# Input_interface.net
KiCad netlist of a schematic drawn in EAGLE
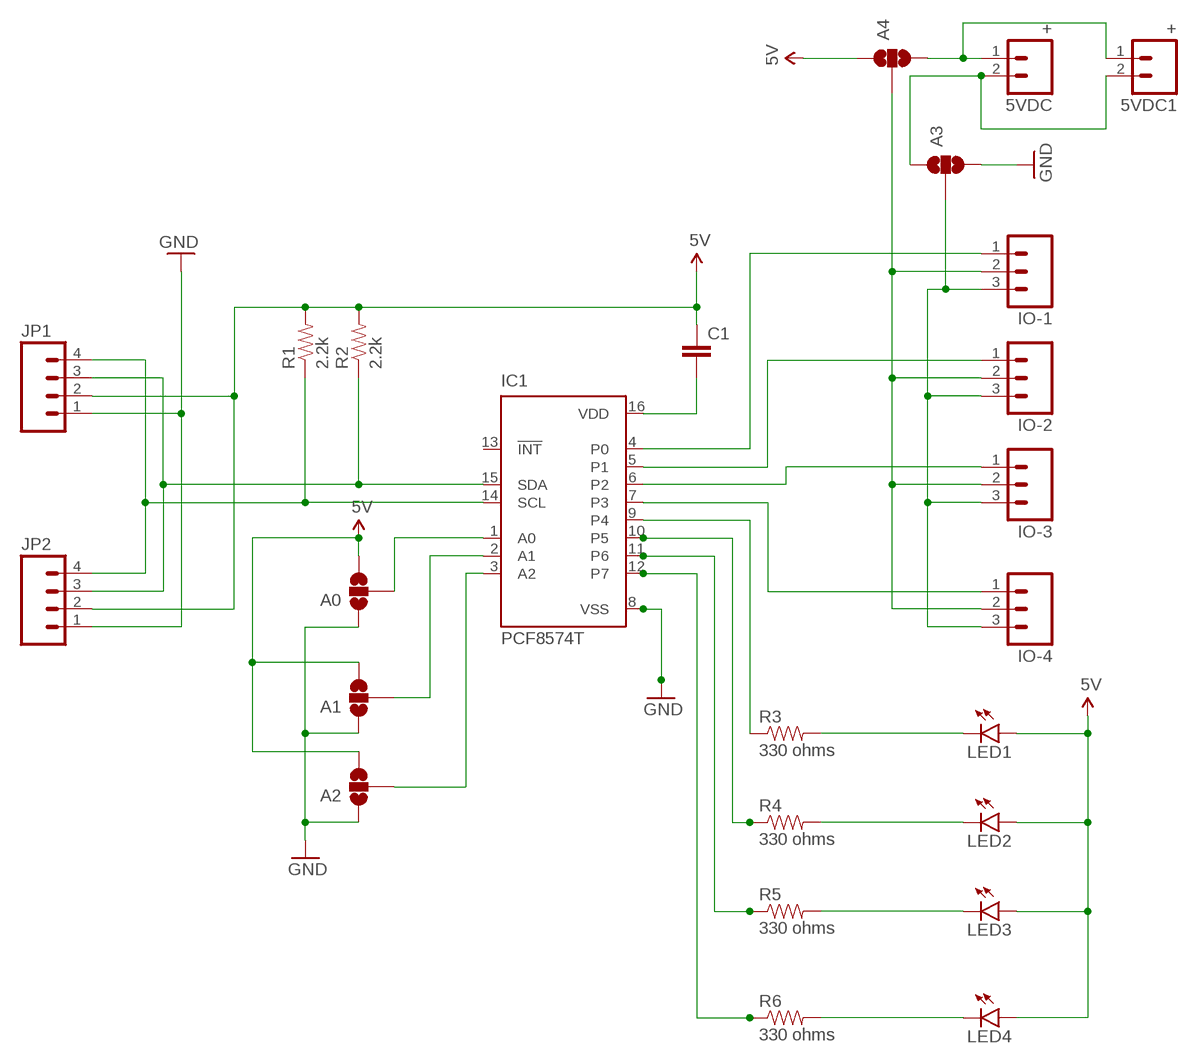
[diagram p0: schematic, sheet 1]

(export (version "E")
  (design (tool "Eeschema 10.0.6"))
  (components
    (comp (ref "5VDC")
      (value "+")
      (footprint "eagle-import:1X02")
      (libsource (lib "eagle-import") (part "M02PTH"))
    )
    (comp (ref "5VDC1")
      (value "+")
      (footprint "eagle-import:1X02")
      (libsource (lib "eagle-import") (part "M02PTH"))
    )
    (comp (ref "A0")
      (value "SOLDERJUMPER_2WAYS")
      (footprint "eagle-import:SJ_3")
      (libsource (lib "eagle-import") (part "SOLDERJUMPER_2WAYS"))
    )
    (comp (ref "A1")
      (value "SOLDERJUMPER_2WAYS")
      (footprint "eagle-import:SJ_3")
      (libsource (lib "eagle-import") (part "SOLDERJUMPER_2WAYS"))
    )
    (comp (ref "A2")
      (value "SOLDERJUMPER_2WAYS")
      (footprint "eagle-import:SJ_3")
      (libsource (lib "eagle-import") (part "SOLDERJUMPER_2WAYS"))
    )
    (comp (ref "A3")
      (value "SOLDERJUMPER_2WAYS")
      (footprint "eagle-import:SJ_3")
      (libsource (lib "eagle-import") (part "SOLDERJUMPER_2WAYS"))
    )
    (comp (ref "A4")
      (value "SOLDERJUMPER_2WAYS")
      (footprint "eagle-import:SJ_3")
      (libsource (lib "eagle-import") (part "SOLDERJUMPER_2WAYS"))
    )
    (comp (ref "C1")
      (value "CAPPTH2")
      (footprint "eagle-import:CAP-PTH-SMALL2")
      (libsource (lib "eagle-import") (part "CAPPTH2"))
    )
    (comp (ref "IC1")
      (value "PCF8574T")
      (footprint "eagle-import:SO16W")
      (libsource (lib "eagle-import") (part "PCF8574T"))
    )
    (comp (ref "IO-1")
      (value "M03PTH")
      (footprint "eagle-import:1X03")
      (libsource (lib "eagle-import") (part "M03PTH"))
    )
    (comp (ref "IO-2")
      (value "M03PTH")
      (footprint "eagle-import:1X03")
      (libsource (lib "eagle-import") (part "M03PTH"))
    )
    (comp (ref "IO-3")
      (value "M03PTH")
      (footprint "eagle-import:1X03")
      (libsource (lib "eagle-import") (part "M03PTH"))
    )
    (comp (ref "IO-4")
      (value "M03PTH")
      (footprint "eagle-import:1X03")
      (libsource (lib "eagle-import") (part "M03PTH"))
    )
    (comp (ref "JP1")
      (value "M04PTH")
      (footprint "eagle-import:1X04")
      (libsource (lib "eagle-import") (part "M04PTH"))
    )
    (comp (ref "JP2")
      (value "M04PTH")
      (footprint "eagle-import:1X04")
      (libsource (lib "eagle-import") (part "M04PTH"))
    )
    (comp (ref "LED1")
      (value "LED3MM")
      (footprint "eagle-import:LED3MM")
      (libsource (lib "eagle-import") (part "LED3MM"))
    )
    (comp (ref "LED2")
      (value "LED3MM")
      (footprint "eagle-import:LED3MM")
      (libsource (lib "eagle-import") (part "LED3MM"))
    )
    (comp (ref "LED3")
      (value "LED3MM")
      (footprint "eagle-import:LED3MM")
      (libsource (lib "eagle-import") (part "LED3MM"))
    )
    (comp (ref "LED4")
      (value "LED3MM")
      (footprint "eagle-import:LED3MM")
      (libsource (lib "eagle-import") (part "LED3MM"))
    )
    (comp (ref "R1")
      (value "2.2k")
      (footprint "eagle-import:AXIAL-0.3")
      (libsource (lib "eagle-import") (part "RESISTORAXIAL-0.3"))
    )
    (comp (ref "R2")
      (value "2.2k")
      (footprint "eagle-import:AXIAL-0.3")
      (libsource (lib "eagle-import") (part "RESISTORAXIAL-0.3"))
    )
    (comp (ref "R3")
      (value "330 ohms")
      (footprint "eagle-import:AXIAL-0.3")
      (libsource (lib "eagle-import") (part "RESISTORAXIAL-0.3"))
    )
    (comp (ref "R4")
      (value "330 ohms")
      (footprint "eagle-import:AXIAL-0.3")
      (libsource (lib "eagle-import") (part "RESISTORAXIAL-0.3"))
    )
    (comp (ref "R5")
      (value "330 ohms")
      (footprint "eagle-import:AXIAL-0.3")
      (libsource (lib "eagle-import") (part "RESISTORAXIAL-0.3"))
    )
    (comp (ref "R6")
      (value "330 ohms")
      (footprint "eagle-import:AXIAL-0.3")
      (libsource (lib "eagle-import") (part "RESISTORAXIAL-0.3"))
    )
  )
  (nets
    (net (code "1") (name "5V") (class "Default")
      (node (ref "A0") (pin "3") (pinfunction "3_3") (pintype "passive"))
      (node (ref "A1") (pin "3") (pinfunction "3_3") (pintype "passive"))
      (node (ref "A2") (pin "3") (pinfunction "3_3") (pintype "passive"))
      (node (ref "A4") (pin "1") (pinfunction "1_1") (pintype "passive"))
      (node (ref "C1") (pin "1") (pinfunction "1_1") (pintype "passive"))
      (node (ref "JP1") (pin "2") (pinfunction "2_2") (pintype "passive"))
      (node (ref "JP2") (pin "2") (pinfunction "2_2") (pintype "passive"))
      (node (ref "LED1") (pin "A") (pinfunction "A_A") (pintype "passive"))
      (node (ref "LED2") (pin "A") (pinfunction "A_A") (pintype "passive"))
      (node (ref "LED3") (pin "A") (pinfunction "A_A") (pintype "passive"))
      (node (ref "LED4") (pin "A") (pinfunction "A_A") (pintype "passive"))
      (node (ref "R1") (pin "P$2") (pinfunction "2_P$2") (pintype "passive"))
      (node (ref "R2") (pin "P$2") (pinfunction "2_P$2") (pintype "passive"))
    )
    (net (code "2") (name "GND") (class "Default")
      (node (ref "A0") (pin "1") (pinfunction "1_1") (pintype "passive"))
      (node (ref "A1") (pin "1") (pinfunction "1_1") (pintype "passive"))
      (node (ref "A2") (pin "1") (pinfunction "1_1") (pintype "passive"))
      (node (ref "A3") (pin "3") (pinfunction "3_3") (pintype "passive"))
      (node (ref "IC1") (pin "8") (pinfunction "VSS_8") (pintype "power_in"))
      (node (ref "JP1") (pin "1") (pinfunction "1_1") (pintype "passive"))
      (node (ref "JP2") (pin "1") (pinfunction "1_1") (pintype "passive"))
    )
    (net (code "3") (name "Net-(5VDC-Pad1)") (class "Default")
      (node (ref "5VDC") (pin "1") (pinfunction "1_1") (pintype "passive"))
      (node (ref "5VDC1") (pin "1") (pinfunction "1_1") (pintype "passive"))
      (node (ref "A4") (pin "3") (pinfunction "3_3") (pintype "passive"))
    )
    (net (code "4") (name "Net-(5VDC-Pad2)") (class "Default")
      (node (ref "5VDC") (pin "2") (pinfunction "2_2") (pintype "passive"))
      (node (ref "5VDC1") (pin "2") (pinfunction "2_2") (pintype "passive"))
      (node (ref "A3") (pin "1") (pinfunction "1_1") (pintype "passive"))
    )
    (net (code "5") (name "Net-(A3-Pad2)") (class "Default")
      (node (ref "A3") (pin "2") (pinfunction "2_2") (pintype "passive"))
      (node (ref "IO-1") (pin "3") (pinfunction "3_3") (pintype "passive"))
      (node (ref "IO-2") (pin "3") (pinfunction "3_3") (pintype "passive"))
      (node (ref "IO-3") (pin "3") (pinfunction "3_3") (pintype "passive"))
      (node (ref "IO-4") (pin "3") (pinfunction "3_3") (pintype "passive"))
    )
    (net (code "6") (name "Net-(A4-Pad2)") (class "Default")
      (node (ref "A4") (pin "2") (pinfunction "2_2") (pintype "passive"))
      (node (ref "IO-1") (pin "2") (pinfunction "2_2") (pintype "passive"))
      (node (ref "IO-2") (pin "2") (pinfunction "2_2") (pintype "passive"))
      (node (ref "IO-3") (pin "2") (pinfunction "2_2") (pintype "passive"))
      (node (ref "IO-4") (pin "2") (pinfunction "2_2") (pintype "passive"))
    )
    (net (code "7") (name "Net-(IC1-A0)") (class "Default")
      (node (ref "A0") (pin "2") (pinfunction "2_2") (pintype "passive"))
      (node (ref "IC1") (pin "1") (pinfunction "A0_1") (pintype "input"))
    )
    (net (code "8") (name "Net-(IC1-A1)") (class "Default")
      (node (ref "A1") (pin "2") (pinfunction "2_2") (pintype "passive"))
      (node (ref "IC1") (pin "2") (pinfunction "A1_2") (pintype "input"))
    )
    (net (code "9") (name "Net-(IC1-A2)") (class "Default")
      (node (ref "A2") (pin "2") (pinfunction "2_2") (pintype "passive"))
      (node (ref "IC1") (pin "3") (pinfunction "A2_3") (pintype "input"))
    )
    (net (code "10") (name "Net-(IC1-P0)") (class "Default")
      (node (ref "IC1") (pin "4") (pinfunction "P0_4") (pintype "bidirectional"))
      (node (ref "IO-1") (pin "1") (pinfunction "1_1") (pintype "passive"))
    )
    (net (code "11") (name "Net-(IC1-P1)") (class "Default")
      (node (ref "IC1") (pin "5") (pinfunction "P1_5") (pintype "bidirectional"))
      (node (ref "IO-2") (pin "1") (pinfunction "1_1") (pintype "passive"))
    )
    (net (code "12") (name "Net-(IC1-P2)") (class "Default")
      (node (ref "IC1") (pin "6") (pinfunction "P2_6") (pintype "bidirectional"))
      (node (ref "IO-3") (pin "1") (pinfunction "1_1") (pintype "passive"))
    )
    (net (code "13") (name "Net-(IC1-P3)") (class "Default")
      (node (ref "IC1") (pin "7") (pinfunction "P3_7") (pintype "bidirectional"))
      (node (ref "IO-4") (pin "1") (pinfunction "1_1") (pintype "passive"))
    )
    (net (code "14") (name "Net-(IC1-P4)") (class "Default")
      (node (ref "IC1") (pin "9") (pinfunction "P4_9") (pintype "bidirectional"))
      (node (ref "R3") (pin "P$1") (pinfunction "1_P$1") (pintype "passive"))
    )
    (net (code "15") (name "Net-(IC1-P5)") (class "Default")
      (node (ref "IC1") (pin "10") (pinfunction "P5_10") (pintype "bidirectional"))
      (node (ref "R4") (pin "P$1") (pinfunction "1_P$1") (pintype "passive"))
    )
    (net (code "16") (name "Net-(IC1-P6)") (class "Default")
      (node (ref "IC1") (pin "11") (pinfunction "P6_11") (pintype "bidirectional"))
      (node (ref "R5") (pin "P$1") (pinfunction "1_P$1") (pintype "passive"))
    )
    (net (code "17") (name "Net-(IC1-P7)") (class "Default")
      (node (ref "IC1") (pin "12") (pinfunction "P7_12") (pintype "bidirectional"))
      (node (ref "R6") (pin "P$1") (pinfunction "1_P$1") (pintype "passive"))
    )
    (net (code "18") (name "Net-(IC1-SCL)") (class "Default")
      (node (ref "IC1") (pin "14") (pinfunction "SCL_14") (pintype "input"))
      (node (ref "JP1") (pin "4") (pinfunction "4_4") (pintype "passive"))
      (node (ref "JP2") (pin "4") (pinfunction "4_4") (pintype "passive"))
      (node (ref "R1") (pin "P$1") (pinfunction "1_P$1") (pintype "passive"))
    )
    (net (code "19") (name "Net-(IC1-SDA)") (class "Default")
      (node (ref "IC1") (pin "15") (pinfunction "SDA_15") (pintype "bidirectional"))
      (node (ref "JP1") (pin "3") (pinfunction "3_3") (pintype "passive"))
      (node (ref "JP2") (pin "3") (pinfunction "3_3") (pintype "passive"))
      (node (ref "R2") (pin "P$1") (pinfunction "1_P$1") (pintype "passive"))
    )
    (net (code "20") (name "Net-(IC1-VDD)") (class "Default")
      (node (ref "C1") (pin "2") (pinfunction "2_2") (pintype "passive"))
      (node (ref "IC1") (pin "16") (pinfunction "VDD_16") (pintype "power_in"))
    )
    (net (code "21") (name "Net-(LED1-C)") (class "Default")
      (node (ref "LED1") (pin "K") (pinfunction "C_K") (pintype "passive"))
      (node (ref "R3") (pin "P$2") (pinfunction "2_P$2") (pintype "passive"))
    )
    (net (code "22") (name "Net-(LED2-C)") (class "Default")
      (node (ref "LED2") (pin "K") (pinfunction "C_K") (pintype "passive"))
      (node (ref "R4") (pin "P$2") (pinfunction "2_P$2") (pintype "passive"))
    )
    (net (code "23") (name "Net-(LED3-C)") (class "Default")
      (node (ref "LED3") (pin "K") (pinfunction "C_K") (pintype "passive"))
      (node (ref "R5") (pin "P$2") (pinfunction "2_P$2") (pintype "passive"))
    )
    (net (code "24") (name "Net-(LED4-C)") (class "Default")
      (node (ref "LED4") (pin "K") (pinfunction "C_K") (pintype "passive"))
      (node (ref "R6") (pin "P$2") (pinfunction "2_P$2") (pintype "passive"))
    )
    (net (code "25") (name "unconnected-(IC1-~{INT}-Pad13)") (class "Default")
      (node (ref "IC1") (pin "13") (pinfunction "~{INT}_13") (pintype "output"))
    )
  )
)
